# Embedded_II_MAIN_BOARD.net
KiCad netlist of a schematic drawn in EAGLE
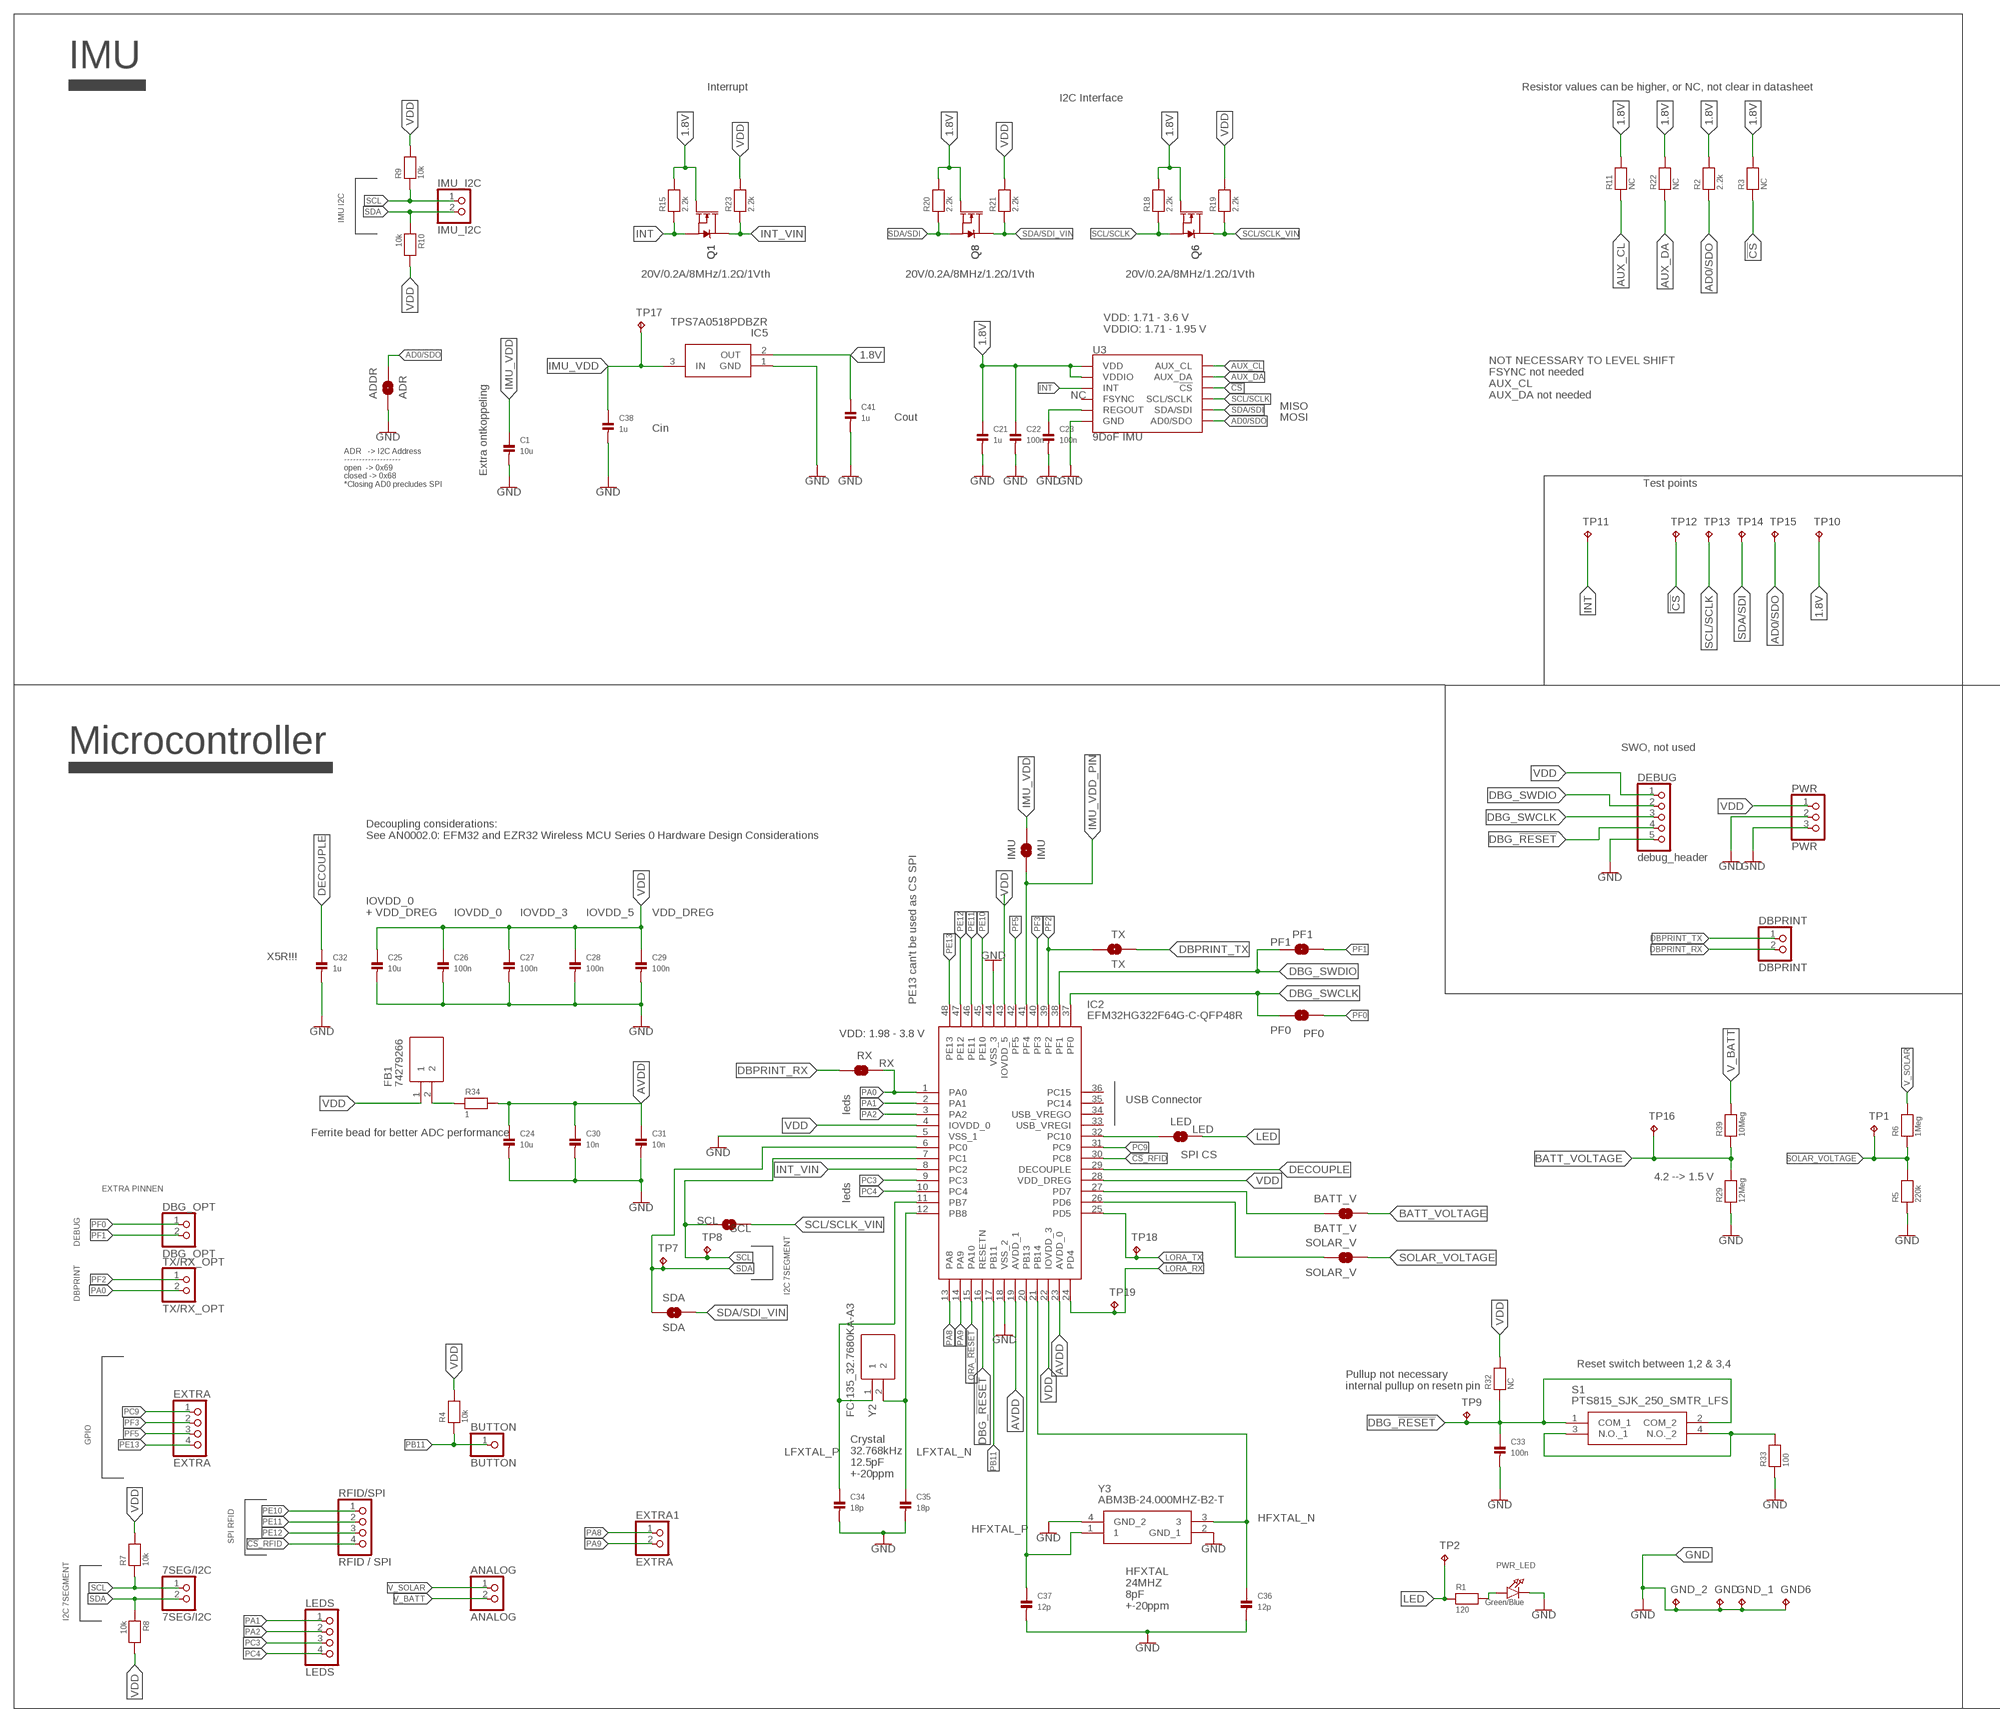
[diagram p0: schematic, sheet 1, part 1 of 2]
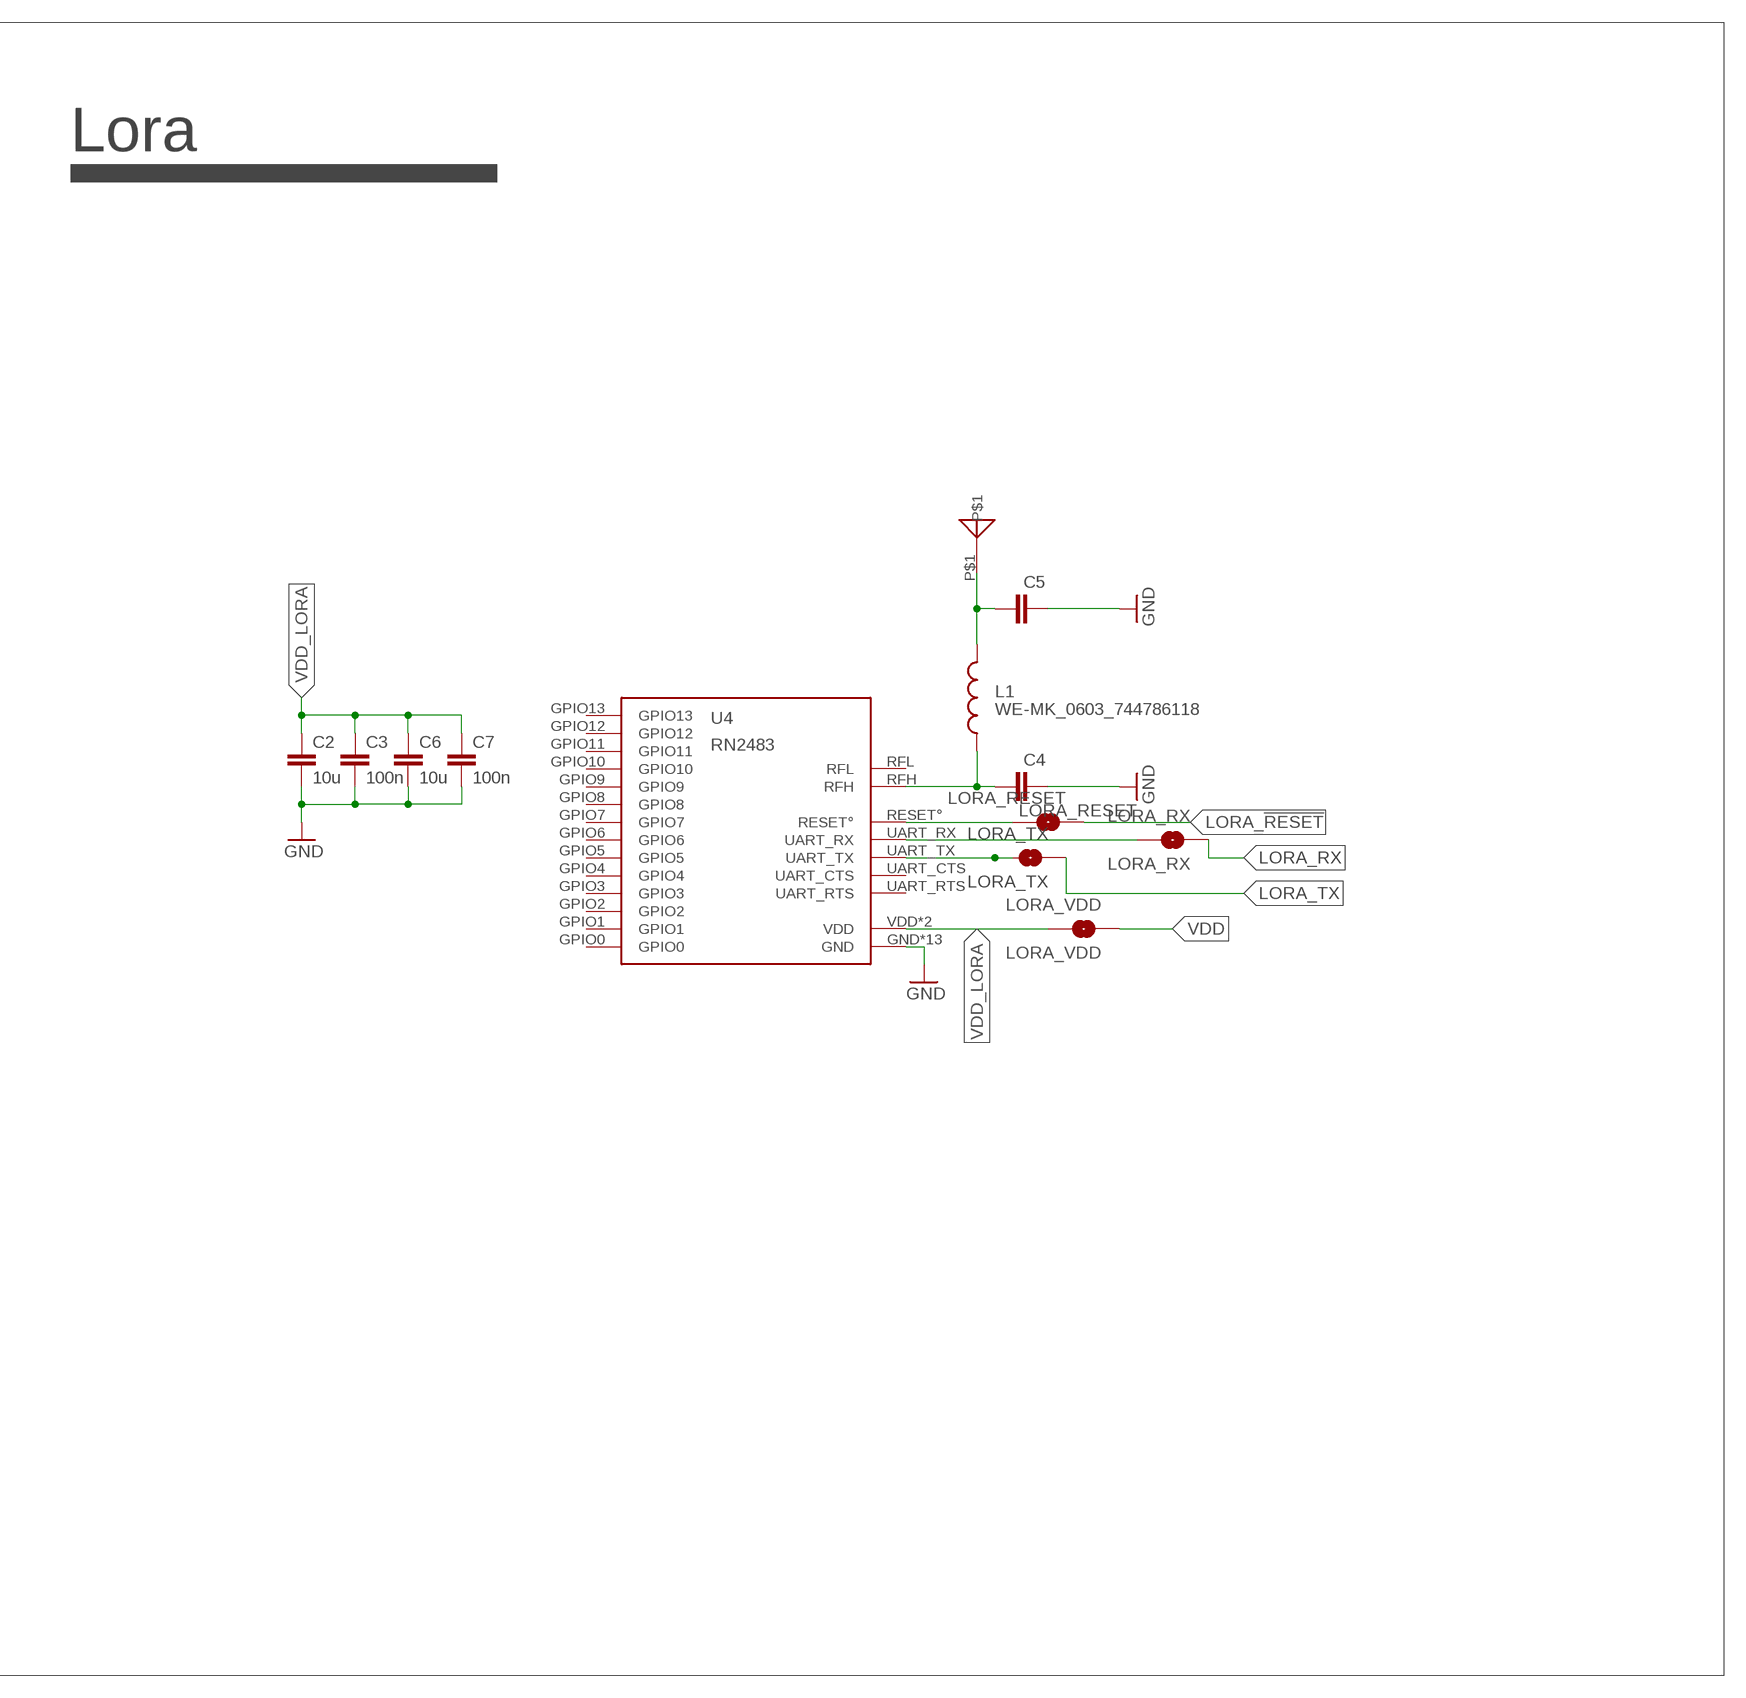
[diagram p1: schematic, sheet 1, part 2 of 2]

(export (version "E")
  (design (tool "Eeschema 10.0.6"))
  (components
    (comp (ref "7SEG/I2C")
      (value "7SEG/I2C")
      (footprint "eagle-import:1X02")
      (libsource (lib "eagle-import") (part "PINHD-1X2"))
    )
    (comp (ref "ADDR")
      (value "ADR")
      (footprint "eagle-import:SMT-JUMPER_2_NO_SILK")
      (libsource (lib "eagle-import") (part "JUMPER-SMT_2_NO_SILK"))
    )
    (comp (ref "ANALOG")
      (value "ANALOG")
      (footprint "eagle-import:1X02")
      (libsource (lib "eagle-import") (part "PINHD-1X2"))
    )
    (comp (ref "BATT_V")
      (value "BATT_V")
      (footprint "eagle-import:SMT-JUMPER_2_NO_SILK")
      (libsource (lib "eagle-import") (part "JUMPER-SMT_2_NO_SILK"))
    )
    (comp (ref "BUTTON")
      (value "BUTTON")
      (footprint "eagle-import:1X01")
      (libsource (lib "eagle-import") (part "PINHD-1X1"))
    )
    (comp (ref "C1")
      (value "10u")
      (footprint "eagle-import:0603")
      (libsource (lib "eagle-import") (part "CAP_CERAMIC0603"))
    )
    (comp (ref "C2")
      (value "10u")
      (footprint "eagle-import:C0805K")
      (libsource (lib "eagle-import") (part "C-EUC0805K"))
    )
    (comp (ref "C3")
      (value "100n")
      (footprint "eagle-import:C0805K")
      (libsource (lib "eagle-import") (part "C-EUC0805K"))
    )
    (comp (ref "C4")
      (value "C-EUC0603K")
      (footprint "eagle-import:C0603K")
      (libsource (lib "eagle-import") (part "C-EUC0603K"))
    )
    (comp (ref "C5")
      (value "C-EUC0603K")
      (footprint "eagle-import:C0603K")
      (libsource (lib "eagle-import") (part "C-EUC0603K"))
    )
    (comp (ref "C6")
      (value "10u")
      (footprint "eagle-import:C0805K")
      (libsource (lib "eagle-import") (part "C-EUC0805K"))
    )
    (comp (ref "C7")
      (value "100n")
      (footprint "eagle-import:C0805K")
      (libsource (lib "eagle-import") (part "C-EUC0805K"))
    )
    (comp (ref "C21")
      (value "1u")
      (footprint "eagle-import:0603")
      (libsource (lib "eagle-import") (part "CAP_CERAMIC0603"))
    )
    (comp (ref "C22")
      (value "100n")
      (footprint "eagle-import:0603")
      (libsource (lib "eagle-import") (part "CAP_CERAMIC0603"))
    )
    (comp (ref "C23")
      (value "100n")
      (footprint "eagle-import:0603")
      (libsource (lib "eagle-import") (part "CAP_CERAMIC0603"))
    )
    (comp (ref "C24")
      (value "10u")
      (footprint "eagle-import:0603")
      (libsource (lib "eagle-import") (part "CAP_CERAMIC0603"))
    )
    (comp (ref "C25")
      (value "10u")
      (footprint "eagle-import:0603")
      (libsource (lib "eagle-import") (part "CAP_CERAMIC0603"))
    )
    (comp (ref "C26")
      (value "100n")
      (footprint "eagle-import:0603")
      (libsource (lib "eagle-import") (part "CAP_CERAMIC0603"))
    )
    (comp (ref "C27")
      (value "100n")
      (footprint "eagle-import:0603")
      (libsource (lib "eagle-import") (part "CAP_CERAMIC0603"))
    )
    (comp (ref "C28")
      (value "100n")
      (footprint "eagle-import:0603")
      (libsource (lib "eagle-import") (part "CAP_CERAMIC0603"))
    )
    (comp (ref "C29")
      (value "100n")
      (footprint "eagle-import:0603")
      (libsource (lib "eagle-import") (part "CAP_CERAMIC0603"))
    )
    (comp (ref "C30")
      (value "10n")
      (footprint "eagle-import:0603")
      (libsource (lib "eagle-import") (part "CAP_CERAMIC0603"))
    )
    (comp (ref "C31")
      (value "10n")
      (footprint "eagle-import:0603")
      (libsource (lib "eagle-import") (part "CAP_CERAMIC0603"))
    )
    (comp (ref "C32")
      (value "1u")
      (footprint "eagle-import:0603")
      (libsource (lib "eagle-import") (part "CAP_CERAMIC0603"))
    )
    (comp (ref "C33")
      (value "100n")
      (footprint "eagle-import:0603")
      (libsource (lib "eagle-import") (part "CAP_CERAMIC0603"))
    )
    (comp (ref "C34")
      (value "18p")
      (footprint "eagle-import:0603")
      (libsource (lib "eagle-import") (part "CAP_CERAMIC0603"))
    )
    (comp (ref "C35")
      (value "18p")
      (footprint "eagle-import:0603")
      (libsource (lib "eagle-import") (part "CAP_CERAMIC0603"))
    )
    (comp (ref "C36")
      (value "12p")
      (footprint "eagle-import:0603")
      (libsource (lib "eagle-import") (part "CAP_CERAMIC0603"))
    )
    (comp (ref "C37")
      (value "12p")
      (footprint "eagle-import:0603")
      (libsource (lib "eagle-import") (part "CAP_CERAMIC0603"))
    )
    (comp (ref "C38")
      (value "1u")
      (footprint "eagle-import:0603")
      (libsource (lib "eagle-import") (part "CAP_CERAMIC0603"))
    )
    (comp (ref "C41")
      (value "1u")
      (footprint "eagle-import:0603")
      (libsource (lib "eagle-import") (part "CAP_CERAMIC0603"))
    )
    (comp (ref "DBG_OPT")
      (value "DBG_OPT")
      (footprint "eagle-import:1X02")
      (libsource (lib "eagle-import") (part "PINHD-1X2"))
    )
    (comp (ref "DBPRINT")
      (value "DBPRINT")
      (footprint "eagle-import:1X02")
      (libsource (lib "eagle-import") (part "PINHD-1X2"))
    )
    (comp (ref "DEBUG")
      (value "debug_header")
      (footprint "eagle-import:1X05")
      (libsource (lib "eagle-import") (part "PINHD-1X5"))
    )
    (comp (ref "EXTRA")
      (value "EXTRA")
      (footprint "eagle-import:1X04")
      (libsource (lib "eagle-import") (part "PINHD-1X4"))
    )
    (comp (ref "EXTRA1")
      (value "EXTRA")
      (footprint "eagle-import:1X02")
      (libsource (lib "eagle-import") (part "PINHD-1X2"))
    )
    (comp (ref "FB1")
      (value "74279266")
      (footprint "eagle-import:BEADC1608X100N")
      (fields (field (name "MOUSER_PART_NUMBER") "710-74279266"))
      (libsource (lib "eagle-import") (part "74279266"))
    )
    (comp (ref "GND")
      (value "TPTP20SQ")
      (footprint "eagle-import:TP20SQ")
      (libsource (lib "eagle-import") (part "TPTP20SQ"))
    )
    (comp (ref "GND6")
      (value "TPTP20SQ")
      (footprint "eagle-import:TP20SQ")
      (libsource (lib "eagle-import") (part "TPTP20SQ"))
    )
    (comp (ref "GND_1")
      (value "TPTP20SQ")
      (footprint "eagle-import:TP20SQ")
      (libsource (lib "eagle-import") (part "TPTP20SQ"))
    )
    (comp (ref "GND_2")
      (value "TPTP20SQ")
      (footprint "eagle-import:TP20SQ")
      (libsource (lib "eagle-import") (part "TPTP20SQ"))
    )
    (comp (ref "IC2")
      (value "EFM32HG322F64G-C-QFP48R")
      (footprint "eagle-import:QFP50P900X900X120-48N")
      (fields (field (name "MOUSER_PART_NUMBER") "634-HG322F64GCQFP48R"))
      (libsource (lib "eagle-import") (part "EFM32HG322F64G-C-QFP48R"))
    )
    (comp (ref "IC5")
      (value "TPS7A0518PDBZR")
      (footprint "eagle-import:SOT95P237X112-3N")
      (fields (field (name "MOUSER_PART_NUMBER") "595-TPS7A0518PDBZR"))
      (libsource (lib "eagle-import") (part "TPS7A0518PDBZR"))
    )
    (comp (ref "IMU")
      (value "IMU")
      (footprint "eagle-import:SMT-JUMPER_2_NO_SILK")
      (libsource (lib "eagle-import") (part "JUMPER-SMT_2_NO_SILK"))
    )
    (comp (ref "IMU_I2C")
      (value "IMU_I2C")
      (footprint "eagle-import:1X02")
      (libsource (lib "eagle-import") (part "PINHD-1X2"))
    )
    (comp (ref "L1")
      (value "WE-MK_0603_744786118")
      (footprint "eagle-import:WE-MK_0603")
      (libsource (lib "eagle-import") (part "WE-MK_0603_744786118"))
    )
    (comp (ref "LED")
      (value "LED")
      (footprint "eagle-import:SMT-JUMPER_2_NO_SILK")
      (libsource (lib "eagle-import") (part "JUMPER-SMT_2_NO_SILK"))
    )
    (comp (ref "LEDS")
      (value "LEDS")
      (footprint "eagle-import:1X04")
      (libsource (lib "eagle-import") (part "PINHD-1X4"))
    )
    (comp (ref "LORA_RESET")
      (value "LORA_RESET")
      (footprint "eagle-import:SMT-JUMPER_2_NO_SILK")
      (libsource (lib "eagle-import") (part "JUMPER-SMT_2_NO_SILK"))
    )
    (comp (ref "LORA_RX")
      (value "LORA_RX")
      (footprint "eagle-import:SMT-JUMPER_2_NO_SILK")
      (libsource (lib "eagle-import") (part "JUMPER-SMT_2_NO_SILK"))
    )
    (comp (ref "LORA_TX")
      (value "LORA_TX")
      (footprint "eagle-import:SMT-JUMPER_2_NO_SILK")
      (libsource (lib "eagle-import") (part "JUMPER-SMT_2_NO_SILK"))
    )
    (comp (ref "LORA_VDD")
      (value "LORA_VDD")
      (footprint "eagle-import:SMT-JUMPER_2_NO_SILK")
      (libsource (lib "eagle-import") (part "JUMPER-SMT_2_NO_SILK"))
    )
    (comp (ref "PF0")
      (value "PF0")
      (footprint "eagle-import:SMT-JUMPER_2_NO_SILK")
      (libsource (lib "eagle-import") (part "JUMPER-SMT_2_NO_SILK"))
    )
    (comp (ref "PF1")
      (value "PF1")
      (footprint "eagle-import:SMT-JUMPER_2_NO_SILK")
      (libsource (lib "eagle-import") (part "JUMPER-SMT_2_NO_SILK"))
    )
    (comp (ref "PWR")
      (value "PWR")
      (footprint "eagle-import:1X03")
      (libsource (lib "eagle-import") (part "PINHD-1X3"))
    )
    (comp (ref "PWR_LED")
      (value "Green/Blue")
      (footprint "eagle-import:CHIPLED_0805")
      (libsource (lib "eagle-import") (part "LED0805"))
    )
    (comp (ref "Q1")
      (value "20V/0.2A/8MHz/1.2Ω/1Vth")
      (footprint "eagle-import:SOT-416FL")
      (libsource (lib "eagle-import") (part "MOSFET-NCH-RE1C002UN"))
    )
    (comp (ref "Q6")
      (value "20V/0.2A/8MHz/1.2Ω/1Vth")
      (footprint "eagle-import:SOT-416FL")
      (libsource (lib "eagle-import") (part "MOSFET-NCH-RE1C002UN"))
    )
    (comp (ref "Q8")
      (value "20V/0.2A/8MHz/1.2Ω/1Vth")
      (footprint "eagle-import:SOT-416FL")
      (libsource (lib "eagle-import") (part "MOSFET-NCH-RE1C002UN"))
    )
    (comp (ref "R1")
      (value "120")
      (footprint "eagle-import:0603")
      (libsource (lib "eagle-import") (part "RESISTOR0603"))
    )
    (comp (ref "R2")
      (value "2.2k")
      (footprint "eagle-import:0603")
      (libsource (lib "eagle-import") (part "RESISTOR0603"))
    )
    (comp (ref "R3")
      (value "NC")
      (footprint "eagle-import:0603")
      (libsource (lib "eagle-import") (part "RESISTOR0603"))
    )
    (comp (ref "R4")
      (value "10k")
      (footprint "eagle-import:0603")
      (libsource (lib "eagle-import") (part "RESISTOR0603"))
    )
    (comp (ref "R5")
      (value "220k")
      (footprint "eagle-import:0603")
      (libsource (lib "eagle-import") (part "RESISTOR0603"))
    )
    (comp (ref "R6")
      (value "1Meg")
      (footprint "eagle-import:0603")
      (libsource (lib "eagle-import") (part "RESISTOR0603"))
    )
    (comp (ref "R7")
      (value "10k")
      (footprint "eagle-import:0603")
      (libsource (lib "eagle-import") (part "RESISTOR0603"))
    )
    (comp (ref "R8")
      (value "10k")
      (footprint "eagle-import:0603")
      (libsource (lib "eagle-import") (part "RESISTOR0603"))
    )
    (comp (ref "R9")
      (value "10k")
      (footprint "eagle-import:0603")
      (libsource (lib "eagle-import") (part "RESISTOR0603"))
    )
    (comp (ref "R10")
      (value "10k")
      (footprint "eagle-import:0603")
      (libsource (lib "eagle-import") (part "RESISTOR0603"))
    )
    (comp (ref "R11")
      (value "NC")
      (footprint "eagle-import:0603")
      (libsource (lib "eagle-import") (part "RESISTOR0603"))
    )
    (comp (ref "R15")
      (value "2.2k")
      (footprint "eagle-import:0603")
      (libsource (lib "eagle-import") (part "RESISTOR0603"))
    )
    (comp (ref "R18")
      (value "2.2k")
      (footprint "eagle-import:0603")
      (libsource (lib "eagle-import") (part "RESISTOR0603"))
    )
    (comp (ref "R19")
      (value "2.2k")
      (footprint "eagle-import:0603")
      (libsource (lib "eagle-import") (part "RESISTOR0603"))
    )
    (comp (ref "R20")
      (value "2.2k")
      (footprint "eagle-import:0603")
      (libsource (lib "eagle-import") (part "RESISTOR0603"))
    )
    (comp (ref "R21")
      (value "2.2k")
      (footprint "eagle-import:0603")
      (libsource (lib "eagle-import") (part "RESISTOR0603"))
    )
    (comp (ref "R22")
      (value "NC")
      (footprint "eagle-import:0603")
      (libsource (lib "eagle-import") (part "RESISTOR0603"))
    )
    (comp (ref "R23")
      (value "2.2k")
      (footprint "eagle-import:0603")
      (libsource (lib "eagle-import") (part "RESISTOR0603"))
    )
    (comp (ref "R29")
      (value "12Meg")
      (footprint "eagle-import:0603")
      (libsource (lib "eagle-import") (part "RESISTOR0603"))
    )
    (comp (ref "R32")
      (value "NC")
      (footprint "eagle-import:0603")
      (libsource (lib "eagle-import") (part "RESISTOR0603"))
    )
    (comp (ref "R33")
      (value "100")
      (footprint "eagle-import:0603")
      (libsource (lib "eagle-import") (part "RESISTOR0603"))
    )
    (comp (ref "R34")
      (value "1")
      (footprint "eagle-import:0603")
      (libsource (lib "eagle-import") (part "RESISTOR0603"))
    )
    (comp (ref "R39")
      (value "10Meg")
      (footprint "eagle-import:0603")
      (libsource (lib "eagle-import") (part "RESISTOR0603"))
    )
    (comp (ref "RFID/SPI")
      (value "RFID / SPI")
      (footprint "eagle-import:1X04")
      (libsource (lib "eagle-import") (part "PINHD-1X4"))
    )
    (comp (ref "RX")
      (value "RX")
      (footprint "eagle-import:SMT-JUMPER_2_NO_SILK")
      (libsource (lib "eagle-import") (part "JUMPER-SMT_2_NO_SILK"))
    )
    (comp (ref "S1")
      (value "PTS815_SJK_250_SMTR_LFS")
      (footprint "eagle-import:PTS815SJK250SMTRLFS")
      (fields
        (field (name "MANUFACTURER_PART_NUMBER") "PTS815 SJK 250 SMTR LFS")
        (field (name "MOUSER_PART_NUMBER") "611-PTS815SJK250SMTR")
      )
      (libsource (lib "eagle-import") (part "PTS815_SJK_250_SMTR_LFS"))
    )
    (comp (ref "SCL")
      (value "SCL")
      (footprint "eagle-import:SMT-JUMPER_2_NO_SILK")
      (libsource (lib "eagle-import") (part "JUMPER-SMT_2_NO_SILK"))
    )
    (comp (ref "SDA")
      (value "SDA")
      (footprint "eagle-import:SMT-JUMPER_2_NO_SILK")
      (libsource (lib "eagle-import") (part "JUMPER-SMT_2_NO_SILK"))
    )
    (comp (ref "SOLAR_V")
      (value "SOLAR_V")
      (footprint "eagle-import:SMT-JUMPER_2_NO_SILK")
      (libsource (lib "eagle-import") (part "JUMPER-SMT_2_NO_SILK"))
    )
    (comp (ref "TP1")
      (value "TPTP10R")
      (footprint "eagle-import:TP10R")
      (libsource (lib "eagle-import") (part "TPTP10R"))
    )
    (comp (ref "TP2")
      (value "TPTP10R")
      (footprint "eagle-import:TP10R")
      (libsource (lib "eagle-import") (part "TPTP10R"))
    )
    (comp (ref "TP7")
      (value "TPTP10R")
      (footprint "eagle-import:TP10R")
      (libsource (lib "eagle-import") (part "TPTP10R"))
    )
    (comp (ref "TP8")
      (value "TPTP10R")
      (footprint "eagle-import:TP10R")
      (libsource (lib "eagle-import") (part "TPTP10R"))
    )
    (comp (ref "TP9")
      (value "TPTP10R")
      (footprint "eagle-import:TP10R")
      (libsource (lib "eagle-import") (part "TPTP10R"))
    )
    (comp (ref "TP10")
      (value "TPTP10R")
      (footprint "eagle-import:TP10R")
      (libsource (lib "eagle-import") (part "TPTP10R"))
    )
    (comp (ref "TP11")
      (value "TPTP10R")
      (footprint "eagle-import:TP10R")
      (libsource (lib "eagle-import") (part "TPTP10R"))
    )
    (comp (ref "TP12")
      (value "TPTP10R")
      (footprint "eagle-import:TP10R")
      (libsource (lib "eagle-import") (part "TPTP10R"))
    )
    (comp (ref "TP13")
      (value "TPTP10R")
      (footprint "eagle-import:TP10R")
      (libsource (lib "eagle-import") (part "TPTP10R"))
    )
    (comp (ref "TP14")
      (value "TPTP10R")
      (footprint "eagle-import:TP10R")
      (libsource (lib "eagle-import") (part "TPTP10R"))
    )
    (comp (ref "TP15")
      (value "TPTP10R")
      (footprint "eagle-import:TP10R")
      (libsource (lib "eagle-import") (part "TPTP10R"))
    )
    (comp (ref "TP16")
      (value "TPTP10R")
      (footprint "eagle-import:TP10R")
      (libsource (lib "eagle-import") (part "TPTP10R"))
    )
    (comp (ref "TP17")
      (value "TPTP10R")
      (footprint "eagle-import:TP10R")
      (libsource (lib "eagle-import") (part "TPTP10R"))
    )
    (comp (ref "TP18")
      (value "TPTP10R")
      (footprint "eagle-import:TP10R")
      (libsource (lib "eagle-import") (part "TPTP10R"))
    )
    (comp (ref "TP19")
      (value "TPTP10R")
      (footprint "eagle-import:TP10R")
      (libsource (lib "eagle-import") (part "TPTP10R"))
    )
    (comp (ref "TX")
      (value "TX")
      (footprint "eagle-import:SMT-JUMPER_2_NO_SILK")
      (libsource (lib "eagle-import") (part "JUMPER-SMT_2_NO_SILK"))
    )
    (comp (ref "TX/RX_OPT")
      (value "TX/RX_OPT")
      (footprint "eagle-import:1X02")
      (libsource (lib "eagle-import") (part "PINHD-1X2"))
    )
    (comp (ref "U$2")
      (value "ANTENNA868")
      (footprint "eagle-import:CERAMIC-ANTENNA")
      (libsource (lib "eagle-import") (part "ANTENNA868"))
    )
    (comp (ref "U3")
      (value "9DoF IMU")
      (footprint "eagle-import:SPARKFUN-SENSORS_QFN24-3X3")
      (libsource (lib "eagle-import") (part "SPARKFUN-SENSORS_ICM-20948"))
    )
    (comp (ref "U4")
      (value "RN2483")
      (footprint "eagle-import:RN2483")
      (libsource (lib "eagle-import") (part "RN2483"))
    )
    (comp (ref "Y2")
      (value "FC-135_32.7680KA-A3")
      (footprint "eagle-import:FC135327680KAAG0")
      (fields
        (field (name "MANUFACTURER_PART_NUMBER") "FC-135 32.7680KA-A3")
        (field (name "MOUSER_PART_NUMBER") "732-FC135-32.76KAA3")
      )
      (libsource (lib "eagle-import") (part "FC-135_32.7680KA-A3"))
    )
    (comp (ref "Y3")
      (value "ABM3B-24.000MHZ-B2-T")
      (footprint "eagle-import:ABM3B8000MHZ101UT")
      (fields (field (name "MOUSER_PART_NUMBER") "815-ABM3B-24-B2"))
      (libsource (lib "eagle-import") (part "ABM3B-24.000MHZ-B2-T"))
    )
  )
  (nets
    (net (code "1") (name "/DBG_~{RESET}") (class "Default")
      (node (ref "C33") (pin "1") (pinfunction "P$1_1") (pintype "passive"))
      (node (ref "DEBUG") (pin "4") (pinfunction "4_4") (pintype "passive"))
      (node (ref "IC2") (pin "16") (pinfunction "RESETN_16") (pintype "bidirectional"))
      (node (ref "R32") (pin "1") (pinfunction "1_1") (pintype "passive"))
      (node (ref "S1") (pin "1") (pinfunction "COM_1_1") (pintype "bidirectional"))
      (node (ref "S1") (pin "2") (pinfunction "COM_2_2") (pintype "bidirectional"))
      (node (ref "TP9") (pin "TP") (pinfunction "TP_TP") (pintype "input"))
    )
    (net (code "2") (name "/LORA_~{RESET}") (class "Default")
      (node (ref "IC2") (pin "15") (pinfunction "PA10_15") (pintype "bidirectional"))
      (node (ref "LORA_RESET") (pin "1") (pinfunction "1_1") (pintype "passive"))
    )
    (net (code "3") (name "/~{CS}") (class "Default")
      (node (ref "R3") (pin "1") (pinfunction "1_1") (pintype "passive"))
      (node (ref "TP12") (pin "TP") (pinfunction "TP_TP") (pintype "input"))
      (node (ref "U3") (pin "22") (pinfunction "~{CS}_22") (pintype "bidirectional"))
    )
    (net (code "4") (name "/~{CS}_RFID") (class "Default")
      (node (ref "IC2") (pin "30") (pinfunction "PC8_30") (pintype "bidirectional"))
      (node (ref "RFID/SPI") (pin "4") (pinfunction "4_4") (pintype "passive"))
    )
    (net (code "5") (name "1.8V") (class "Default")
      (node (ref "C21") (pin "1") (pinfunction "P$1_1") (pintype "passive"))
      (node (ref "C22") (pin "1") (pinfunction "P$1_1") (pintype "passive"))
      (node (ref "C41") (pin "1") (pinfunction "P$1_1") (pintype "passive"))
      (node (ref "IC5") (pin "2") (pinfunction "OUT_2") (pintype "bidirectional"))
      (node (ref "Q1") (pin "1") (pinfunction "G_1") (pintype "bidirectional"))
      (node (ref "Q6") (pin "1") (pinfunction "G_1") (pintype "bidirectional"))
      (node (ref "Q8") (pin "1") (pinfunction "G_1") (pintype "bidirectional"))
      (node (ref "R11") (pin "2") (pinfunction "2_2") (pintype "passive"))
      (node (ref "R15") (pin "2") (pinfunction "2_2") (pintype "passive"))
      (node (ref "R18") (pin "2") (pinfunction "2_2") (pintype "passive"))
      (node (ref "R2") (pin "2") (pinfunction "2_2") (pintype "passive"))
      (node (ref "R20") (pin "2") (pinfunction "2_2") (pintype "passive"))
      (node (ref "R22") (pin "2") (pinfunction "2_2") (pintype "passive"))
      (node (ref "R3") (pin "2") (pinfunction "2_2") (pintype "passive"))
      (node (ref "TP10") (pin "TP") (pinfunction "TP_TP") (pintype "input"))
      (node (ref "U3") (pin "13") (pinfunction "VDD_13") (pintype "bidirectional"))
      (node (ref "U3") (pin "8") (pinfunction "VDDIO_8") (pintype "bidirectional"))
    )
    (net (code "6") (name "AD0{slash}SDO") (class "Default")
      (node (ref "ADDR") (pin "2") (pinfunction "2_2") (pintype "passive"))
      (node (ref "R2") (pin "1") (pinfunction "1_1") (pintype "passive"))
      (node (ref "TP15") (pin "TP") (pinfunction "TP_TP") (pintype "input"))
      (node (ref "U3") (pin "9") (pinfunction "AD0/SDO_9") (pintype "bidirectional"))
    )
    (net (code "7") (name "AUX_CL") (class "Default")
      (node (ref "R11") (pin "1") (pinfunction "1_1") (pintype "passive"))
      (node (ref "U3") (pin "7") (pinfunction "AUX_CL_7") (pintype "bidirectional"))
    )
    (net (code "8") (name "AUX_DA") (class "Default")
      (node (ref "R22") (pin "1") (pinfunction "1_1") (pintype "passive"))
      (node (ref "U3") (pin "21") (pinfunction "AUX_DA_21") (pintype "bidirectional"))
    )
    (net (code "9") (name "AVDD") (class "Default")
      (node (ref "C24") (pin "1") (pinfunction "P$1_1") (pintype "passive"))
      (node (ref "C30") (pin "1") (pinfunction "P$1_1") (pintype "passive"))
      (node (ref "C31") (pin "1") (pinfunction "P$1_1") (pintype "passive"))
      (node (ref "IC2") (pin "19") (pinfunction "AVDD_1_19") (pintype "bidirectional"))
      (node (ref "IC2") (pin "23") (pinfunction "AVDD_0_23") (pintype "bidirectional"))
      (node (ref "R34") (pin "2") (pinfunction "2_2") (pintype "passive"))
    )
    (net (code "10") (name "BATT_VOLTAGE") (class "Default")
      (node (ref "BATT_V") (pin "1") (pinfunction "1_1") (pintype "passive"))
      (node (ref "R29") (pin "2") (pinfunction "2_2") (pintype "passive"))
      (node (ref "R39") (pin "1") (pinfunction "1_1") (pintype "passive"))
      (node (ref "TP16") (pin "TP") (pinfunction "TP_TP") (pintype "input"))
    )
    (net (code "11") (name "DBG_SWCLK") (class "Default")
      (node (ref "DEBUG") (pin "3") (pinfunction "3_3") (pintype "passive"))
      (node (ref "IC2") (pin "37") (pinfunction "PF0_37") (pintype "bidirectional"))
      (node (ref "PF0") (pin "2") (pinfunction "2_2") (pintype "passive"))
    )
    (net (code "12") (name "DBG_SWDIO") (class "Default")
      (node (ref "DEBUG") (pin "2") (pinfunction "2_2") (pintype "passive"))
      (node (ref "IC2") (pin "38") (pinfunction "PF1_38") (pintype "bidirectional"))
      (node (ref "PF1") (pin "2") (pinfunction "2_2") (pintype "passive"))
    )
    (net (code "13") (name "DBPRINT_RX") (class "Default")
      (node (ref "DBPRINT") (pin "2") (pinfunction "2_2") (pintype "passive"))
      (node (ref "RX") (pin "2") (pinfunction "2_2") (pintype "passive"))
    )
    (net (code "14") (name "DBPRINT_TX") (class "Default")
      (node (ref "DBPRINT") (pin "1") (pinfunction "1_1") (pintype "passive"))
      (node (ref "TX") (pin "1") (pinfunction "1_1") (pintype "passive"))
    )
    (net (code "15") (name "DECOUPLE") (class "Default")
      (node (ref "C32") (pin "1") (pinfunction "P$1_1") (pintype "passive"))
      (node (ref "IC2") (pin "29") (pinfunction "DECOUPLE_29") (pintype "bidirectional"))
    )
    (net (code "16") (name "GND") (class "Default")
      (node (ref "ADDR") (pin "1") (pinfunction "1_1") (pintype "passive"))
      (node (ref "C1") (pin "2") (pinfunction "P$2_2") (pintype "passive"))
      (node (ref "C2") (pin "2") (pinfunction "2_2") (pintype "passive"))
      (node (ref "C21") (pin "2") (pinfunction "P$2_2") (pintype "passive"))
      (node (ref "C22") (pin "2") (pinfunction "P$2_2") (pintype "passive"))
      (node (ref "C23") (pin "2") (pinfunction "P$2_2") (pintype "passive"))
      (node (ref "C24") (pin "2") (pinfunction "P$2_2") (pintype "passive"))
      (node (ref "C25") (pin "2") (pinfunction "P$2_2") (pintype "passive"))
      (node (ref "C26") (pin "2") (pinfunction "P$2_2") (pintype "passive"))
      (node (ref "C27") (pin "2") (pinfunction "P$2_2") (pintype "passive"))
      (node (ref "C28") (pin "2") (pinfunction "P$2_2") (pintype "passive"))
      (node (ref "C29") (pin "2") (pinfunction "P$2_2") (pintype "passive"))
      (node (ref "C3") (pin "2") (pinfunction "2_2") (pintype "passive"))
      (node (ref "C30") (pin "2") (pinfunction "P$2_2") (pintype "passive"))
      (node (ref "C31") (pin "2") (pinfunction "P$2_2") (pintype "passive"))
      (node (ref "C32") (pin "2") (pinfunction "P$2_2") (pintype "passive"))
      (node (ref "C33") (pin "2") (pinfunction "P$2_2") (pintype "passive"))
      (node (ref "C34") (pin "2") (pinfunction "P$2_2") (pintype "passive"))
      (node (ref "C35") (pin "2") (pinfunction "P$2_2") (pintype "passive"))
      (node (ref "C36") (pin "2") (pinfunction "P$2_2") (pintype "passive"))
      (node (ref "C37") (pin "2") (pinfunction "P$2_2") (pintype "passive"))
      (node (ref "C38") (pin "2") (pinfunction "P$2_2") (pintype "passive"))
      (node (ref "C4") (pin "1") (pinfunction "1_1") (pintype "passive"))
      (node (ref "C41") (pin "2") (pinfunction "P$2_2") (pintype "passive"))
      (node (ref "C5") (pin "1") (pinfunction "1_1") (pintype "passive"))
      (node (ref "C6") (pin "2") (pinfunction "2_2") (pintype "passive"))
      (node (ref "C7") (pin "2") (pinfunction "2_2") (pintype "passive"))
      (node (ref "DEBUG") (pin "5") (pinfunction "5_5") (pintype "passive"))
      (node (ref "GND") (pin "TP") (pinfunction "TP_TP") (pintype "input"))
      (node (ref "GND6") (pin "TP") (pinfunction "TP_TP") (pintype "input"))
      (node (ref "GND_1") (pin "TP") (pinfunction "TP_TP") (pintype "input"))
      (node (ref "GND_2") (pin "TP") (pinfunction "TP_TP") (pintype "input"))
      (node (ref "IC2") (pin "18") (pinfunction "VSS_2_18") (pintype "bidirectional"))
      (node (ref "IC2") (pin "44") (pinfunction "VSS_3_44") (pintype "bidirectional"))
      (node (ref "IC2") (pin "5") (pinfunction "VSS_1_5") (pintype "bidirectional"))
      (node (ref "IC5") (pin "1") (pinfunction "GND_1") (pintype "bidirectional"))
      (node (ref "PWR") (pin "2") (pinfunction "2_2") (pintype "passive"))
      (node (ref "PWR") (pin "3") (pinfunction "3_3") (pintype "passive"))
      (node (ref "PWR_LED") (pin "C") (pinfunction "C_C") (pintype "passive"))
      (node (ref "R29") (pin "1") (pinfunction "1_1") (pintype "passive"))
      (node (ref "R33") (pin "1") (pinfunction "1_1") (pintype "passive"))
      (node (ref "R5") (pin "1") (pinfunction "1_1") (pintype "passive"))
      (node (ref "U3") (pin "18") (pinfunction "GND_18") (pintype "bidirectional"))
      (node (ref "U3") (pin "20") (pinfunction "GND_20") (pintype "bidirectional"))
      (node (ref "U4") (pin "GND") (pinfunction "GND_GND") (pintype "bidirectional"))
      (node (ref "U4") (pin "GND1") (pinfunction "GND_GND1") (pintype "bidirectional"))
      (node (ref "U4") (pin "GND10") (pinfunction "GND_GND10") (pintype "bidirectional"))
      (node (ref "U4") (pin "GND11") (pinfunction "GND_GND11") (pintype "bidirectional"))
      (node (ref "U4") (pin "GND12") (pinfunction "GND_GND12") (pintype "bidirectional"))
      (node (ref "U4") (pin "GND2") (pinfunction "GND_GND2") (pintype "bidirectional"))
      (node (ref "U4") (pin "GND3") (pinfunction "GND_GND3") (pintype "bidirectional"))
      (node (ref "U4") (pin "GND4") (pinfunction "GND_GND4") (pintype "bidirectional"))
      (node (ref "U4") (pin "GND5") (pinfunction "GND_GND5") (pintype "bidirectional"))
      (node (ref "U4") (pin "GND6") (pinfunction "GND_GND6") (pintype "bidirectional"))
      (node (ref "U4") (pin "GND7") (pinfunction "GND_GND7") (pintype "bidirectional"))
      (node (ref "U4") (pin "GND8") (pinfunction "GND_GND8") (pintype "bidirectional"))
      (node (ref "U4") (pin "GND9") (pinfunction "GND_GND9") (pintype "bidirectional"))
      (node (ref "Y3") (pin "2") (pinfunction "GND_1_2") (pintype "bidirectional"))
      (node (ref "Y3") (pin "4") (pinfunction "GND_2_4") (pintype "bidirectional"))
    )
    (net (code "17") (name "IMU_VDD") (class "Default")
      (node (ref "C1") (pin "1") (pinfunction "P$1_1") (pintype "passive"))
      (node (ref "C38") (pin "1") (pinfunction "P$1_1") (pintype "passive"))
      (node (ref "IC5") (pin "3") (pinfunction "IN_3") (pintype "bidirectional"))
      (node (ref "IMU") (pin "1") (pinfunction "1_1") (pintype "passive"))
      (node (ref "TP17") (pin "TP") (pinfunction "TP_TP") (pintype "input"))
    )
    (net (code "18") (name "IMU_VDD_PIN") (class "Default")
      (node (ref "IC2") (pin "41") (pinfunction "PF4_41") (pintype "bidirectional"))
      (node (ref "IMU") (pin "2") (pinfunction "2_2") (pintype "passive"))
    )
    (net (code "19") (name "INT") (class "Default")
      (node (ref "Q1") (pin "2") (pinfunction "S_2") (pintype "bidirectional"))
      (node (ref "R15") (pin "1") (pinfunction "1_1") (pintype "passive"))
      (node (ref "TP11") (pin "TP") (pinfunction "TP_TP") (pintype "input"))
      (node (ref "U3") (pin "12") (pinfunction "INT_12") (pintype "bidirectional"))
    )
    (net (code "20") (name "INT_VIN") (class "Default")
      (node (ref "IC2") (pin "8") (pinfunction "PC2_8") (pintype "bidirectional"))
      (node (ref "Q1") (pin "3") (pinfunction "D_3") (pintype "bidirectional"))
      (node (ref "R23") (pin "1") (pinfunction "1_1") (pintype "passive"))
    )
    (net (code "21") (name "LED") (class "Default")
      (node (ref "LED") (pin "1") (pinfunction "1_1") (pintype "passive"))
      (node (ref "R1") (pin "1") (pinfunction "1_1") (pintype "passive"))
      (node (ref "TP2") (pin "TP") (pinfunction "TP_TP") (pintype "input"))
    )
    (net (code "22") (name "LORA_RX") (class "Default")
      (node (ref "IC2") (pin "24") (pinfunction "PD4_24") (pintype "bidirectional"))
      (node (ref "LORA_RX") (pin "1") (pinfunction "1_1") (pintype "passive"))
      (node (ref "TP19") (pin "TP") (pinfunction "TP_TP") (pintype "input"))
    )
    (net (code "23") (name "LORA_TX") (class "Default")
      (node (ref "IC2") (pin "25") (pinfunction "PD5_25") (pintype "bidirectional"))
      (node (ref "LORA_TX") (pin "1") (pinfunction "1_1") (pintype "passive"))
      (node (ref "TP18") (pin "TP") (pinfunction "TP_TP") (pintype "input"))
    )
    (net (code "24") (name "Net-(C4-Pad2)") (class "Default")
      (node (ref "C4") (pin "2") (pinfunction "2_2") (pintype "passive"))
      (node (ref "L1") (pin "1") (pinfunction "1_1") (pintype "passive"))
      (node (ref "U4") (pin "RFH") (pinfunction "RFH_RFH") (pintype "bidirectional"))
    )
    (net (code "25") (name "Net-(C5-Pad2)") (class "Default")
      (node (ref "C5") (pin "2") (pinfunction "2_2") (pintype "passive"))
      (node (ref "L1") (pin "2") (pinfunction "2_2") (pintype "passive"))
      (node (ref "U$2") (pin "P$1") (pinfunction "P$1_P$1") (pintype "bidirectional"))
    )
    (net (code "26") (name "Net-(C23-P$1)") (class "Default")
      (node (ref "C23") (pin "1") (pinfunction "P$1_1") (pintype "passive"))
      (node (ref "U3") (pin "10") (pinfunction "REGOUT_10") (pintype "bidirectional"))
    )
    (net (code "27") (name "Net-(C34-P$1)") (class "Default")
      (node (ref "C34") (pin "1") (pinfunction "P$1_1") (pintype "passive"))
      (node (ref "IC2") (pin "11") (pinfunction "PB7_11") (pintype "bidirectional"))
      (node (ref "Y2") (pin "1") (pinfunction "1_1") (pintype "bidirectional"))
    )
    (net (code "28") (name "Net-(C35-P$1)") (class "Default")
      (node (ref "C35") (pin "1") (pinfunction "P$1_1") (pintype "passive"))
      (node (ref "IC2") (pin "12") (pinfunction "PB8_12") (pintype "bidirectional"))
      (node (ref "Y2") (pin "2") (pinfunction "2_2") (pintype "bidirectional"))
    )
    (net (code "29") (name "Net-(C36-P$1)") (class "Default")
      (node (ref "C36") (pin "1") (pinfunction "P$1_1") (pintype "passive"))
      (node (ref "IC2") (pin "21") (pinfunction "PB14_21") (pintype "bidirectional"))
      (node (ref "Y3") (pin "3") (pinfunction "3_3") (pintype "bidirectional"))
    )
    (net (code "30") (name "Net-(C37-P$1)") (class "Default")
      (node (ref "C37") (pin "1") (pinfunction "P$1_1") (pintype "passive"))
      (node (ref "IC2") (pin "20") (pinfunction "PB13_20") (pintype "bidirectional"))
      (node (ref "Y3") (pin "1") (pinfunction "1_1") (pintype "bidirectional"))
    )
    (net (code "31") (name "Net-(FB1-Pad2)") (class "Default")
      (node (ref "FB1") (pin "2") (pinfunction "2_2") (pintype "bidirectional"))
      (node (ref "R34") (pin "1") (pinfunction "1_1") (pintype "passive"))
    )
    (net (code "32") (name "Net-(IC2-PC10)") (class "Default")
      (node (ref "IC2") (pin "32") (pinfunction "PC10_32") (pintype "bidirectional"))
      (node (ref "LED") (pin "2") (pinfunction "2_2") (pintype "passive"))
    )
    (net (code "33") (name "Net-(IC2-PD6)") (class "Default")
      (node (ref "IC2") (pin "26") (pinfunction "PD6_26") (pintype "bidirectional"))
      (node (ref "SOLAR_V") (pin "2") (pinfunction "2_2") (pintype "passive"))
    )
    (net (code "34") (name "Net-(IC2-PD7)") (class "Default")
      (node (ref "BATT_V") (pin "2") (pinfunction "2_2") (pintype "passive"))
      (node (ref "IC2") (pin "27") (pinfunction "PD7_27") (pintype "bidirectional"))
    )
    (net (code "35") (name "Net-(LORA_RESET-Pad2)") (class "Default")
      (node (ref "LORA_RESET") (pin "2") (pinfunction "2_2") (pintype "passive"))
      (node (ref "U4") (pin "RESET°") (pinfunction "RESET°_RESET°") (pintype "bidirectional"))
    )
    (net (code "36") (name "Net-(LORA_RX-Pad2)") (class "Default")
      (node (ref "LORA_RX") (pin "2") (pinfunction "2_2") (pintype "passive"))
      (node (ref "U4") (pin "UART_RX") (pinfunction "UART_RX_UART_RX") (pintype "bidirectional"))
    )
    (net (code "37") (name "Net-(LORA_TX-Pad2)") (class "Default")
      (node (ref "LORA_TX") (pin "2") (pinfunction "2_2") (pintype "passive"))
      (node (ref "U4") (pin "UART_TX") (pinfunction "UART_TX_UART_TX") (pintype "bidirectional"))
    )
    (net (code "38") (name "Net-(PWR_LED-PadA)") (class "Default")
      (node (ref "PWR_LED") (pin "A") (pinfunction "A_A") (pintype "passive"))
      (node (ref "R1") (pin "2") (pinfunction "2_2") (pintype "passive"))
    )
    (net (code "39") (name "Net-(S1-N.O._1)") (class "Default")
      (node (ref "R33") (pin "2") (pinfunction "2_2") (pintype "passive"))
      (node (ref "S1") (pin "3") (pinfunction "N.O._1_3") (pintype "bidirectional"))
      (node (ref "S1") (pin "4") (pinfunction "N.O._2_4") (pintype "bidirectional"))
    )
    (net (code "40") (name "PA0") (class "Default")
      (node (ref "IC2") (pin "1") (pinfunction "PA0_1") (pintype "bidirectional"))
      (node (ref "RX") (pin "1") (pinfunction "1_1") (pintype "passive"))
      (node (ref "TX/RX_OPT") (pin "2") (pinfunction "2_2") (pintype "passive"))
    )
    (net (code "41") (name "PA1") (class "Default")
      (node (ref "IC2") (pin "2") (pinfunction "PA1_2") (pintype "bidirectional"))
      (node (ref "LEDS") (pin "1") (pinfunction "1_1") (pintype "passive"))
    )
    (net (code "42") (name "PA2") (class "Default")
      (node (ref "IC2") (pin "3") (pinfunction "PA2_3") (pintype "bidirectional"))
      (node (ref "LEDS") (pin "2") (pinfunction "2_2") (pintype "passive"))
    )
    (net (code "43") (name "PA8") (class "Default")
      (node (ref "EXTRA1") (pin "1") (pinfunction "1_1") (pintype "passive"))
      (node (ref "IC2") (pin "13") (pinfunction "PA8_13") (pintype "bidirectional"))
    )
    (net (code "44") (name "PA9") (class "Default")
      (node (ref "EXTRA1") (pin "2") (pinfunction "2_2") (pintype "passive"))
      (node (ref "IC2") (pin "14") (pinfunction "PA9_14") (pintype "bidirectional"))
    )
    (net (code "45") (name "PB11") (class "Default")
      (node (ref "BUTTON") (pin "1") (pinfunction "1_1") (pintype "passive"))
      (node (ref "IC2") (pin "17") (pinfunction "PB11_17") (pintype "bidirectional"))
      (node (ref "R4") (pin "1") (pinfunction "1_1") (pintype "passive"))
    )
    (net (code "46") (name "PC3") (class "Default")
      (node (ref "IC2") (pin "9") (pinfunction "PC3_9") (pintype "bidirectional"))
      (node (ref "LEDS") (pin "3") (pinfunction "3_3") (pintype "passive"))
    )
    (net (code "47") (name "PC4") (class "Default")
      (node (ref "IC2") (pin "10") (pinfunction "PC4_10") (pintype "bidirectional"))
      (node (ref "LEDS") (pin "4") (pinfunction "4_4") (pintype "passive"))
    )
    (net (code "48") (name "PC9") (class "Default")
      (node (ref "EXTRA") (pin "1") (pinfunction "1_1") (pintype "passive"))
      (node (ref "IC2") (pin "31") (pinfunction "PC9_31") (pintype "bidirectional"))
    )
    (net (code "49") (name "PE10") (class "Default")
      (node (ref "IC2") (pin "45") (pinfunction "PE10_45") (pintype "bidirectional"))
      (node (ref "RFID/SPI") (pin "1") (pinfunction "1_1") (pintype "passive"))
    )
    (net (code "50") (name "PE11") (class "Default")
      (node (ref "IC2") (pin "46") (pinfunction "PE11_46") (pintype "bidirectional"))
      (node (ref "RFID/SPI") (pin "2") (pinfunction "2_2") (pintype "passive"))
    )
    (net (code "51") (name "PE12") (class "Default")
      (node (ref "IC2") (pin "47") (pinfunction "PE12_47") (pintype "bidirectional"))
      (node (ref "RFID/SPI") (pin "3") (pinfunction "3_3") (pintype "passive"))
    )
    (net (code "52") (name "PE13") (class "Default")
      (node (ref "EXTRA") (pin "4") (pinfunction "4_4") (pintype "passive"))
      (node (ref "IC2") (pin "48") (pinfunction "PE13_48") (pintype "bidirectional"))
    )
    (net (code "53") (name "PF0") (class "Default")
      (node (ref "DBG_OPT") (pin "1") (pinfunction "1_1") (pintype "passive"))
      (node (ref "PF0") (pin "1") (pinfunction "1_1") (pintype "passive"))
    )
    (net (code "54") (name "PF1") (class "Default")
      (node (ref "DBG_OPT") (pin "2") (pinfunction "2_2") (pintype "passive"))
      (node (ref "PF1") (pin "1") (pinfunction "1_1") (pintype "passive"))
    )
    (net (code "55") (name "PF2") (class "Default")
      (node (ref "IC2") (pin "39") (pinfunction "PF2_39") (pintype "bidirectional"))
      (node (ref "TX") (pin "2") (pinfunction "2_2") (pintype "passive"))
      (node (ref "TX/RX_OPT") (pin "1") (pinfunction "1_1") (pintype "passive"))
    )
    (net (code "56") (name "PF3") (class "Default")
      (node (ref "EXTRA") (pin "2") (pinfunction "2_2") (pintype "passive"))
      (node (ref "IC2") (pin "40") (pinfunction "PF3_40") (pintype "bidirectional"))
    )
    (net (code "57") (name "PF5") (class "Default")
      (node (ref "EXTRA") (pin "3") (pinfunction "3_3") (pintype "passive"))
      (node (ref "IC2") (pin "42") (pinfunction "PF5_42") (pintype "bidirectional"))
    )
    (net (code "58") (name "SCL") (class "Default")
      (node (ref "7SEG/I2C") (pin "1") (pinfunction "1_1") (pintype "passive"))
      (node (ref "IC2") (pin "7") (pinfunction "PC1_7") (pintype "bidirectional"))
      (node (ref "IMU_I2C") (pin "1") (pinfunction "1_1") (pintype "passive"))
      (node (ref "R7") (pin "1") (pinfunction "1_1") (pintype "passive"))
      (node (ref "R9") (pin "1") (pinfunction "1_1") (pintype "passive"))
      (node (ref "SCL") (pin "2") (pinfunction "2_2") (pintype "passive"))
      (node (ref "TP8") (pin "TP") (pinfunction "TP_TP") (pintype "input"))
    )
    (net (code "59") (name "SCL{slash}SCLK") (class "Default")
      (node (ref "Q6") (pin "2") (pinfunction "S_2") (pintype "bidirectional"))
      (node (ref "R18") (pin "1") (pinfunction "1_1") (pintype "passive"))
      (node (ref "TP13") (pin "TP") (pinfunction "TP_TP") (pintype "input"))
      (node (ref "U3") (pin "23") (pinfunction "SCL/SCLK_23") (pintype "bidirectional"))
    )
    (net (code "60") (name "SCL{slash}SCLK_VIN") (class "Default")
      (node (ref "Q6") (pin "3") (pinfunction "D_3") (pintype "bidirectional"))
      (node (ref "R19") (pin "1") (pinfunction "1_1") (pintype "passive"))
      (node (ref "SCL") (pin "1") (pinfunction "1_1") (pintype "passive"))
    )
    (net (code "61") (name "SDA") (class "Default")
      (node (ref "7SEG/I2C") (pin "2") (pinfunction "2_2") (pintype "passive"))
      (node (ref "IC2") (pin "6") (pinfunction "PC0_6") (pintype "bidirectional"))
      (node (ref "IMU_I2C") (pin "2") (pinfunction "2_2") (pintype "passive"))
      (node (ref "R10") (pin "1") (pinfunction "1_1") (pintype "passive"))
      (node (ref "R8") (pin "1") (pinfunction "1_1") (pintype "passive"))
      (node (ref "SDA") (pin "2") (pinfunction "2_2") (pintype "passive"))
      (node (ref "TP7") (pin "TP") (pinfunction "TP_TP") (pintype "input"))
    )
    (net (code "62") (name "SDA{slash}SDI") (class "Default")
      (node (ref "Q8") (pin "2") (pinfunction "S_2") (pintype "bidirectional"))
      (node (ref "R20") (pin "1") (pinfunction "1_1") (pintype "passive"))
      (node (ref "TP14") (pin "TP") (pinfunction "TP_TP") (pintype "input"))
      (node (ref "U3") (pin "24") (pinfunction "SDA/SDI_24") (pintype "bidirectional"))
    )
    (net (code "63") (name "SDA{slash}SDI_VIN") (class "Default")
      (node (ref "Q8") (pin "3") (pinfunction "D_3") (pintype "bidirectional"))
      (node (ref "R21") (pin "1") (pinfunction "1_1") (pintype "passive"))
      (node (ref "SDA") (pin "1") (pinfunction "1_1") (pintype "passive"))
    )
    (net (code "64") (name "SOLAR_VOLTAGE") (class "Default")
      (node (ref "R5") (pin "2") (pinfunction "2_2") (pintype "passive"))
      (node (ref "R6") (pin "1") (pinfunction "1_1") (pintype "passive"))
      (node (ref "SOLAR_V") (pin "1") (pinfunction "1_1") (pintype "passive"))
      (node (ref "TP1") (pin "TP") (pinfunction "TP_TP") (pintype "input"))
    )
    (net (code "65") (name "VDD") (class "Default")
      (node (ref "C25") (pin "1") (pinfunction "P$1_1") (pintype "passive"))
      (node (ref "C26") (pin "1") (pinfunction "P$1_1") (pintype "passive"))
      (node (ref "C27") (pin "1") (pinfunction "P$1_1") (pintype "passive"))
      (node (ref "C28") (pin "1") (pinfunction "P$1_1") (pintype "passive"))
      (node (ref "C29") (pin "1") (pinfunction "P$1_1") (pintype "passive"))
      (node (ref "DEBUG") (pin "1") (pinfunction "1_1") (pintype "passive"))
      (node (ref "FB1") (pin "1") (pinfunction "1_1") (pintype "bidirectional"))
      (node (ref "IC2") (pin "22") (pinfunction "IOVDD_3_22") (pintype "bidirectional"))
      (node (ref "IC2") (pin "28") (pinfunction "VDD_DREG_28") (pintype "bidirectional"))
      (node (ref "IC2") (pin "4") (pinfunction "IOVDD_0_4") (pintype "bidirectional"))
      (node (ref "IC2") (pin "43") (pinfunction "IOVDD_5_43") (pintype "bidirectional"))
      (node (ref "LORA_VDD") (pin "1") (pinfunction "1_1") (pintype "passive"))
      (node (ref "PWR") (pin "1") (pinfunction "1_1") (pintype "passive"))
      (node (ref "R10") (pin "2") (pinfunction "2_2") (pintype "passive"))
      (node (ref "R19") (pin "2") (pinfunction "2_2") (pintype "passive"))
      (node (ref "R21") (pin "2") (pinfunction "2_2") (pintype "passive"))
      (node (ref "R23") (pin "2") (pinfunction "2_2") (pintype "passive"))
      (node (ref "R32") (pin "2") (pinfunction "2_2") (pintype "passive"))
      (node (ref "R4") (pin "2") (pinfunction "2_2") (pintype "passive"))
      (node (ref "R7") (pin "2") (pinfunction "2_2") (pintype "passive"))
      (node (ref "R8") (pin "2") (pinfunction "2_2") (pintype "passive"))
      (node (ref "R9") (pin "2") (pinfunction "2_2") (pintype "passive"))
    )
    (net (code "66") (name "VDD_LORA") (class "Default")
      (node (ref "C2") (pin "1") (pinfunction "1_1") (pintype "passive"))
      (node (ref "C3") (pin "1") (pinfunction "1_1") (pintype "passive"))
      (node (ref "C6") (pin "1") (pinfunction "1_1") (pintype "passive"))
      (node (ref "C7") (pin "1") (pinfunction "1_1") (pintype "passive"))
      (node (ref "LORA_VDD") (pin "2") (pinfunction "2_2") (pintype "passive"))
      (node (ref "U4") (pin "VDD") (pinfunction "VDD_VDD") (pintype "bidirectional"))
      (node (ref "U4") (pin "VDD2") (pinfunction "VDD_VDD2") (pintype "bidirectional"))
    )
    (net (code "67") (name "V_BATT") (class "Default")
      (node (ref "ANALOG") (pin "2") (pinfunction "2_2") (pintype "passive"))
      (node (ref "R39") (pin "2") (pinfunction "2_2") (pintype "passive"))
    )
    (net (code "68") (name "V_SOLAR") (class "Default")
      (node (ref "ANALOG") (pin "1") (pinfunction "1_1") (pintype "passive"))
      (node (ref "R6") (pin "2") (pinfunction "2_2") (pintype "passive"))
    )
    (net (code "69") (name "unconnected-(IC2-PC14-Pad35)") (class "Default")
      (node (ref "IC2") (pin "35") (pinfunction "PC14_35") (pintype "bidirectional"))
    )
    (net (code "70") (name "unconnected-(IC2-PC15-Pad36)") (class "Default")
      (node (ref "IC2") (pin "36") (pinfunction "PC15_36") (pintype "bidirectional"))
    )
    (net (code "71") (name "unconnected-(IC2-USB_VREGI-Pad33)") (class "Default")
      (node (ref "IC2") (pin "33") (pinfunction "USB_VREGI_33") (pintype "bidirectional"))
    )
    (net (code "72") (name "unconnected-(IC2-USB_VREGO-Pad34)") (class "Default")
      (node (ref "IC2") (pin "34") (pinfunction "USB_VREGO_34") (pintype "bidirectional"))
    )
    (net (code "73") (name "unconnected-(U3-FSYNC-Pad11)") (class "Default")
      (node (ref "U3") (pin "11") (pinfunction "FSYNC_11") (pintype "bidirectional"))
    )
    (net (code "74") (name "unconnected-(U4-PadGPIO0)") (class "Default")
      (node (ref "U4") (pin "GPIO0") (pinfunction "GPIO0_GPIO0") (pintype "bidirectional"))
    )
    (net (code "75") (name "unconnected-(U4-PadGPIO1)") (class "Default")
      (node (ref "U4") (pin "GPIO1") (pinfunction "GPIO1_GPIO1") (pintype "bidirectional"))
    )
    (net (code "76") (name "unconnected-(U4-PadGPIO2)") (class "Default")
      (node (ref "U4") (pin "GPIO2") (pinfunction "GPIO2_GPIO2") (pintype "bidirectional"))
    )
    (net (code "77") (name "unconnected-(U4-PadGPIO3)") (class "Default")
      (node (ref "U4") (pin "GPIO3") (pinfunction "GPIO3_GPIO3") (pintype "bidirectional"))
    )
    (net (code "78") (name "unconnected-(U4-PadGPIO4)") (class "Default")
      (node (ref "U4") (pin "GPIO4") (pinfunction "GPIO4_GPIO4") (pintype "bidirectional"))
    )
    (net (code "79") (name "unconnected-(U4-PadGPIO5)") (class "Default")
      (node (ref "U4") (pin "GPIO5") (pinfunction "GPIO5_GPIO5") (pintype "bidirectional"))
    )
    (net (code "80") (name "unconnected-(U4-PadGPIO6)") (class "Default")
      (node (ref "U4") (pin "GPIO6") (pinfunction "GPIO6_GPIO6") (pintype "bidirectional"))
    )
    (net (code "81") (name "unconnected-(U4-PadGPIO7)") (class "Default")
      (node (ref "U4") (pin "GPIO7") (pinfunction "GPIO7_GPIO7") (pintype "bidirectional"))
    )
    (net (code "82") (name "unconnected-(U4-PadGPIO8)") (class "Default")
      (node (ref "U4") (pin "GPIO8") (pinfunction "GPIO8_GPIO8") (pintype "bidirectional"))
    )
    (net (code "83") (name "unconnected-(U4-PadGPIO9)") (class "Default")
      (node (ref "U4") (pin "GPIO9") (pinfunction "GPIO9_GPIO9") (pintype "bidirectional"))
    )
    (net (code "84") (name "unconnected-(U4-PadGPIO10)") (class "Default")
      (node (ref "U4") (pin "GPIO10") (pinfunction "GPIO10_GPIO10") (pintype "bidirectional"))
    )
    (net (code "85") (name "unconnected-(U4-PadGPIO11)") (class "Default")
      (node (ref "U4") (pin "GPIO11") (pinfunction "GPIO11_GPIO11") (pintype "bidirectional"))
    )
    (net (code "86") (name "unconnected-(U4-PadGPIO12)") (class "Default")
      (node (ref "U4") (pin "GPIO12") (pinfunction "GPIO12_GPIO12") (pintype "bidirectional"))
    )
    (net (code "87") (name "unconnected-(U4-PadGPIO13)") (class "Default")
      (node (ref "U4") (pin "GPIO13") (pinfunction "GPIO13_GPIO13") (pintype "bidirectional"))
    )
    (net (code "88") (name "unconnected-(U4-PadRFL)") (class "Default")
      (node (ref "U4") (pin "RFL") (pinfunction "RFL_RFL") (pintype "bidirectional"))
    )
    (net (code "89") (name "unconnected-(U4-PadUART_CTS)") (class "Default")
      (node (ref "U4") (pin "UART_CTS") (pinfunction "UART_CTS_UART_CTS") (pintype "bidirectional"))
    )
    (net (code "90") (name "unconnected-(U4-PadUART_RTS)") (class "Default")
      (node (ref "U4") (pin "UART_RTS") (pinfunction "UART_RTS_UART_RTS") (pintype "bidirectional"))
    )
  )
)
